# Fuente.net
KiCad netlist of a schematic drawn in Altium Designer
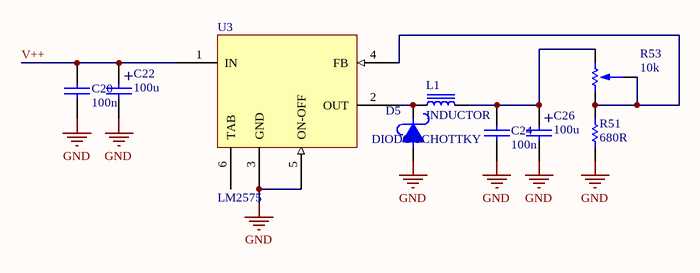
[diagram p0: Fuente.SchDoc]

(export (version "E")
  (design (tool "Eeschema 10.0.6"))
  (components
    (comp (ref "C20") (value "100n") (footprint "CAP200") (libsource (lib "LIBEBAL") (part "CAP")))
    (comp (ref "C22") (value "100u") (footprint "CAP200RP2") (libsource (lib "LIBEBAL") (part "CAPPOL")))
    (comp (ref "C24") (value "100n") (footprint "CAP200") (libsource (lib "LIBEBAL") (part "CAP")))
    (comp (ref "C26") (value "100u") (footprint "CAP200RP2") (libsource (lib "LIBEBAL") (part "CAPPOL")))
    (comp (ref "D5")
      (value "DIODO SCHOTTKY")
      (footprint "DO41")
      (libsource (lib "LIBEBAL") (part "DIODO SCHOTTKY"))
    )
    (comp (ref "L1") (value "INDUCTOR") (footprint "L_IHLP") (libsource (lib "LIBEBAL") (part "INDUCTOR")))
    (comp (ref "R51")
      (value "680R")
      (footprint "1206")
      (description "RES SMD 1/2W 1206")
      (libsource (lib "LIBEBAL") (part "RES"))
    )
    (comp (ref "R53") (value "10k") (footprint "PRESET V") (libsource (lib "LIBEBAL") (part "PRESET")))
    (comp (ref "U3") (value "LM2575") (footprint "TO263") (libsource (lib "LIBEBAL") (part "LM2575")))
  )
  (nets
    (net (code "1") (name "/V++") (class "Default")
      (node (ref "C20") (pin "2") (pinfunction "2_2") (pintype "passive"))
      (node (ref "C22") (pin "1") (pinfunction "1_1") (pintype "passive"))
      (node (ref "U3") (pin "1") (pinfunction "IN_1") (pintype "power_in"))
    )
    (net (code "2") (name "GND") (class "Default")
      (node (ref "C20") (pin "1") (pinfunction "1_1") (pintype "passive"))
      (node (ref "C22") (pin "2") (pinfunction "2_2") (pintype "passive"))
      (node (ref "C24") (pin "1") (pinfunction "1_1") (pintype "passive"))
      (node (ref "C26") (pin "2") (pinfunction "2_2") (pintype "passive"))
      (node (ref "D5") (pin "1") (pinfunction "1_1") (pintype "passive"))
      (node (ref "R51") (pin "2") (pinfunction "2_2") (pintype "passive"))
      (node (ref "U3") (pin "3") (pinfunction "GND_3") (pintype "power_in"))
      (node (ref "U3") (pin "5") (pinfunction "ON-OFF_5") (pintype "input"))
    )
    (net (code "3") (name "Net-(C24-Pad2)") (class "Default")
      (node (ref "C24") (pin "2") (pinfunction "2_2") (pintype "passive"))
      (node (ref "C26") (pin "1") (pinfunction "1_1") (pintype "passive"))
      (node (ref "L1") (pin "2") (pinfunction "2_2") (pintype "passive"))
      (node (ref "R53") (pin "1") (pinfunction "1_1") (pintype "passive"))
    )
    (net (code "4") (name "Net-(U3-FB)") (class "Default")
      (node (ref "R51") (pin "1") (pinfunction "1_1") (pintype "passive"))
      (node (ref "R53") (pin "2") (pinfunction "2_2") (pintype "passive"))
      (node (ref "R53") (pin "3") (pinfunction "3_3") (pintype "passive"))
      (node (ref "U3") (pin "4") (pinfunction "FB_4") (pintype "input"))
    )
    (net (code "5") (name "Net-(U3-OUT)") (class "Default")
      (node (ref "D5") (pin "2") (pinfunction "2_2") (pintype "passive"))
      (node (ref "L1") (pin "1") (pinfunction "1_1") (pintype "passive"))
      (node (ref "U3") (pin "2") (pinfunction "OUT_2") (pintype "power_in"))
    )
    (net (code "6") (name "unconnected-(U3-TAB-Pad6)") (class "Default")
      (node (ref "U3") (pin "6") (pinfunction "TAB_6") (pintype "power_in"))
    )
  )
)
